# VG_CONN.net
KiCad netlist of a schematic drawn in Altium Designer
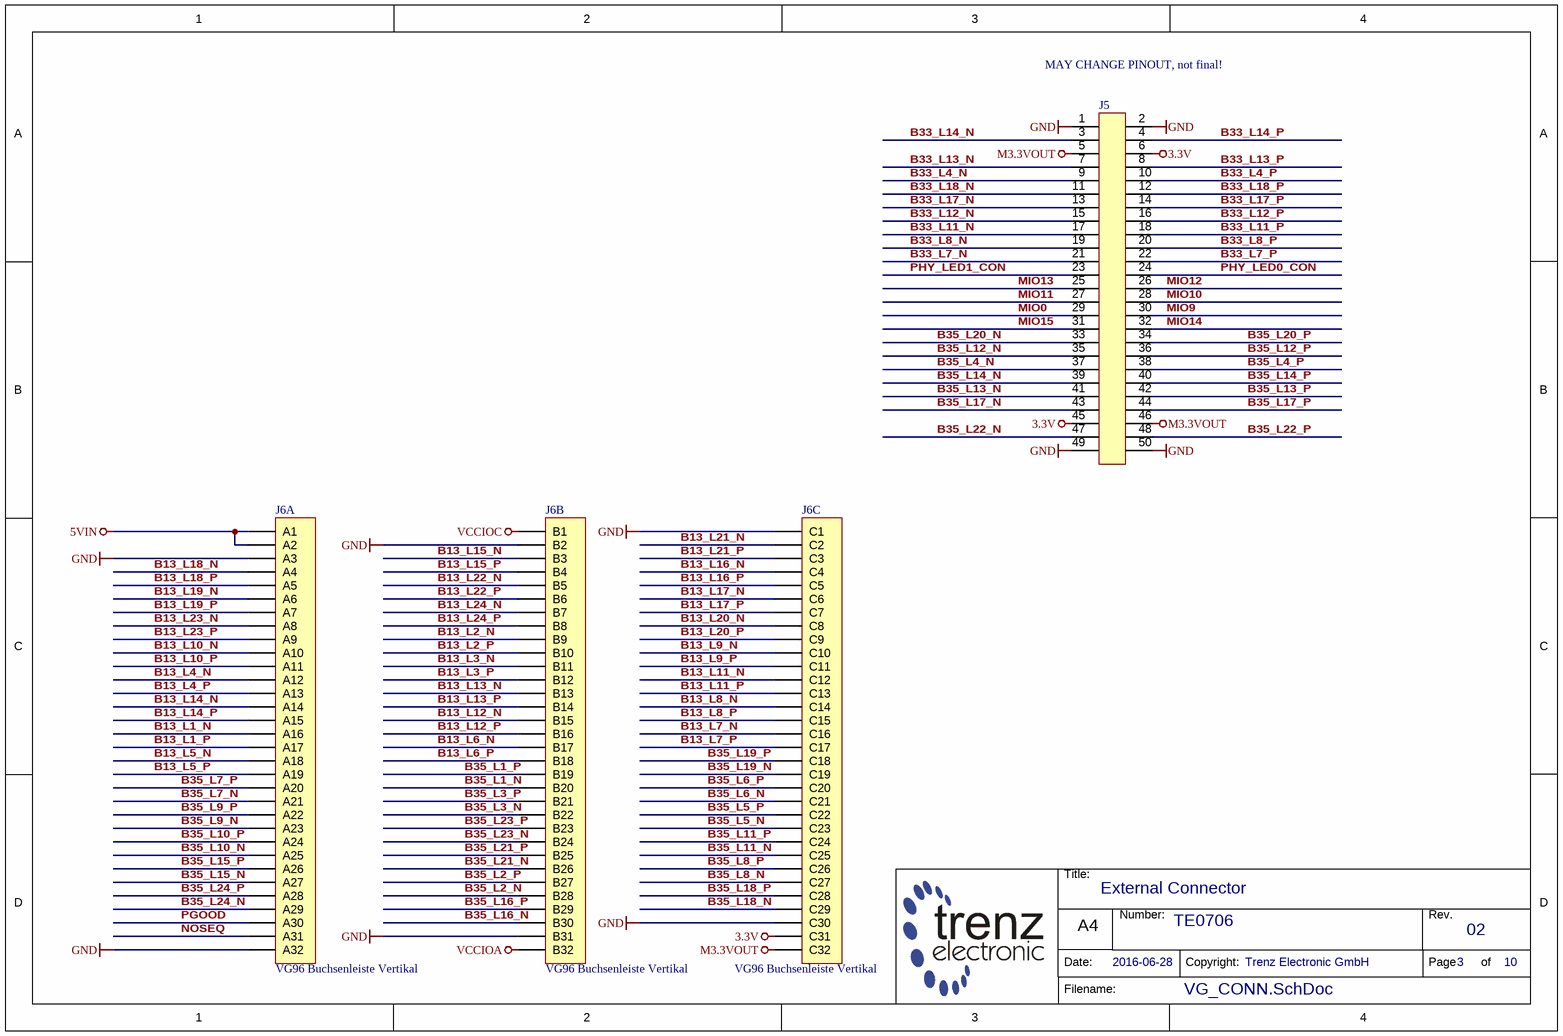
[diagram p0: VG_CONN.SchDoc]

(export (version "E")
  (design (tool "Eeschema 10.0.6"))
  (components
    (comp (ref "J5")
      (value "WANNE2,54-50 GERADE")
      (footprint "WANNE2,54-50 GERADE")
      (description "Stiftleiste Wanne 50polig")
      (libsource (lib "TE") (part "CON-50"))
    )
    (comp (ref "J6")
      (value "VG96 Buchsenleiste Vertikal")
      (footprint "VG96-F-V")
      (description "VG96 Buchsenleiste Vertikal (DIN 41612)")
      (libsource (lib "TE") (part "VG96"))
    )
  )
  (nets
    (net (code "1") (name "/B13_L1_N") (class "Default")
      (node (ref "J6") (pin "A16") (pinfunction "A16_A16") (pintype "passive"))
    )
    (net (code "2") (name "/B13_L1_P") (class "Default")
      (node (ref "J6") (pin "A17") (pinfunction "A17_A17") (pintype "passive"))
    )
    (net (code "3") (name "/B13_L2_N") (class "Default")
      (node (ref "J6") (pin "B9") (pinfunction "B9_B9") (pintype "passive"))
    )
    (net (code "4") (name "/B13_L2_P") (class "Default")
      (node (ref "J6") (pin "B10") (pinfunction "B10_B10") (pintype "passive"))
    )
    (net (code "5") (name "/B13_L3_N") (class "Default")
      (node (ref "J6") (pin "B11") (pinfunction "B11_B11") (pintype "passive"))
    )
    (net (code "6") (name "/B13_L3_P") (class "Default")
      (node (ref "J6") (pin "B12") (pinfunction "B12_B12") (pintype "passive"))
    )
    (net (code "7") (name "/B13_L4_N") (class "Default")
      (node (ref "J6") (pin "A12") (pinfunction "A12_A12") (pintype "passive"))
    )
    (net (code "8") (name "/B13_L4_P") (class "Default")
      (node (ref "J6") (pin "A13") (pinfunction "A13_A13") (pintype "passive"))
    )
    (net (code "9") (name "/B13_L5_N") (class "Default")
      (node (ref "J6") (pin "A18") (pinfunction "A18_A18") (pintype "passive"))
    )
    (net (code "10") (name "/B13_L5_P") (class "Default")
      (node (ref "J6") (pin "A19") (pinfunction "A19_A19") (pintype "passive"))
    )
    (net (code "11") (name "/B13_L6_N") (class "Default")
      (node (ref "J6") (pin "B17") (pinfunction "B17_B17") (pintype "passive"))
    )
    (net (code "12") (name "/B13_L6_P") (class "Default")
      (node (ref "J6") (pin "B18") (pinfunction "B18_B18") (pintype "passive"))
    )
    (net (code "13") (name "/B13_L7_N") (class "Default")
      (node (ref "J6") (pin "C16") (pinfunction "C16_C16") (pintype "passive"))
    )
    (net (code "14") (name "/B13_L7_P") (class "Default")
      (node (ref "J6") (pin "C17") (pinfunction "C17_C17") (pintype "passive"))
    )
    (net (code "15") (name "/B13_L8_N") (class "Default")
      (node (ref "J6") (pin "C14") (pinfunction "C14_C14") (pintype "passive"))
    )
    (net (code "16") (name "/B13_L8_P") (class "Default")
      (node (ref "J6") (pin "C15") (pinfunction "C15_C15") (pintype "passive"))
    )
    (net (code "17") (name "/B13_L9_N") (class "Default")
      (node (ref "J6") (pin "C10") (pinfunction "C10_C10") (pintype "passive"))
    )
    (net (code "18") (name "/B13_L9_P") (class "Default")
      (node (ref "J6") (pin "C11") (pinfunction "C11_C11") (pintype "passive"))
    )
    (net (code "19") (name "/B13_L10_N") (class "Default")
      (node (ref "J6") (pin "A10") (pinfunction "A10_A10") (pintype "passive"))
    )
    (net (code "20") (name "/B13_L10_P") (class "Default")
      (node (ref "J6") (pin "A11") (pinfunction "A11_A11") (pintype "passive"))
    )
    (net (code "21") (name "/B13_L11_N") (class "Default")
      (node (ref "J6") (pin "C12") (pinfunction "C12_C12") (pintype "passive"))
    )
    (net (code "22") (name "/B13_L11_P") (class "Default")
      (node (ref "J6") (pin "C13") (pinfunction "C13_C13") (pintype "passive"))
    )
    (net (code "23") (name "/B13_L12_N") (class "Default")
      (node (ref "J6") (pin "B15") (pinfunction "B15_B15") (pintype "passive"))
    )
    (net (code "24") (name "/B13_L12_P") (class "Default")
      (node (ref "J6") (pin "B16") (pinfunction "B16_B16") (pintype "passive"))
    )
    (net (code "25") (name "/B13_L13_N") (class "Default")
      (node (ref "J6") (pin "B13") (pinfunction "B13_B13") (pintype "passive"))
    )
    (net (code "26") (name "/B13_L13_P") (class "Default")
      (node (ref "J6") (pin "B14") (pinfunction "B14_B14") (pintype "passive"))
    )
    (net (code "27") (name "/B13_L14_N") (class "Default")
      (node (ref "J6") (pin "A14") (pinfunction "A14_A14") (pintype "passive"))
    )
    (net (code "28") (name "/B13_L14_P") (class "Default")
      (node (ref "J6") (pin "A15") (pinfunction "A15_A15") (pintype "passive"))
    )
    (net (code "29") (name "/B13_L15_N") (class "Default")
      (node (ref "J6") (pin "B3") (pinfunction "B3_B3") (pintype "passive"))
    )
    (net (code "30") (name "/B13_L15_P") (class "Default")
      (node (ref "J6") (pin "B4") (pinfunction "B4_B4") (pintype "passive"))
    )
    (net (code "31") (name "/B13_L16_N") (class "Default")
      (node (ref "J6") (pin "C4") (pinfunction "C4_C4") (pintype "passive"))
    )
    (net (code "32") (name "/B13_L16_P") (class "Default")
      (node (ref "J6") (pin "C5") (pinfunction "C5_C5") (pintype "passive"))
    )
    (net (code "33") (name "/B13_L17_N") (class "Default")
      (node (ref "J6") (pin "C6") (pinfunction "C6_C6") (pintype "passive"))
    )
    (net (code "34") (name "/B13_L17_P") (class "Default")
      (node (ref "J6") (pin "C7") (pinfunction "C7_C7") (pintype "passive"))
    )
    (net (code "35") (name "/B13_L18_N") (class "Default")
      (node (ref "J6") (pin "A4") (pinfunction "A4_A4") (pintype "passive"))
    )
    (net (code "36") (name "/B13_L18_P") (class "Default")
      (node (ref "J6") (pin "A5") (pinfunction "A5_A5") (pintype "passive"))
    )
    (net (code "37") (name "/B13_L19_N") (class "Default")
      (node (ref "J6") (pin "A6") (pinfunction "A6_A6") (pintype "passive"))
    )
    (net (code "38") (name "/B13_L19_P") (class "Default")
      (node (ref "J6") (pin "A7") (pinfunction "A7_A7") (pintype "passive"))
    )
    (net (code "39") (name "/B13_L20_N") (class "Default")
      (node (ref "J6") (pin "C8") (pinfunction "C8_C8") (pintype "passive"))
    )
    (net (code "40") (name "/B13_L20_P") (class "Default")
      (node (ref "J6") (pin "C9") (pinfunction "C9_C9") (pintype "passive"))
    )
    (net (code "41") (name "/B13_L21_N") (class "Default")
      (node (ref "J6") (pin "C2") (pinfunction "C2_C2") (pintype "passive"))
    )
    (net (code "42") (name "/B13_L21_P") (class "Default")
      (node (ref "J6") (pin "C3") (pinfunction "C3_C3") (pintype "passive"))
    )
    (net (code "43") (name "/B13_L22_N") (class "Default")
      (node (ref "J6") (pin "B5") (pinfunction "B5_B5") (pintype "passive"))
    )
    (net (code "44") (name "/B13_L22_P") (class "Default")
      (node (ref "J6") (pin "B6") (pinfunction "B6_B6") (pintype "passive"))
    )
    (net (code "45") (name "/B13_L23_N") (class "Default")
      (node (ref "J6") (pin "A8") (pinfunction "A8_A8") (pintype "passive"))
    )
    (net (code "46") (name "/B13_L23_P") (class "Default")
      (node (ref "J6") (pin "A9") (pinfunction "A9_A9") (pintype "passive"))
    )
    (net (code "47") (name "/B13_L24_N") (class "Default")
      (node (ref "J6") (pin "B7") (pinfunction "B7_B7") (pintype "passive"))
    )
    (net (code "48") (name "/B13_L24_P") (class "Default")
      (node (ref "J6") (pin "B8") (pinfunction "B8_B8") (pintype "passive"))
    )
    (net (code "49") (name "/B33_L4_N") (class "Default")
      (node (ref "J5") (pin "9") (pinfunction "9_9") (pintype "passive"))
    )
    (net (code "50") (name "/B33_L4_P") (class "Default")
      (node (ref "J5") (pin "10") (pinfunction "10_10") (pintype "passive"))
    )
    (net (code "51") (name "/B33_L7_N") (class "Default")
      (node (ref "J5") (pin "21") (pinfunction "21_21") (pintype "passive"))
    )
    (net (code "52") (name "/B33_L7_P") (class "Default")
      (node (ref "J5") (pin "22") (pinfunction "22_22") (pintype "passive"))
    )
    (net (code "53") (name "/B33_L8_N") (class "Default")
      (node (ref "J5") (pin "19") (pinfunction "19_19") (pintype "passive"))
    )
    (net (code "54") (name "/B33_L8_P") (class "Default")
      (node (ref "J5") (pin "20") (pinfunction "20_20") (pintype "passive"))
    )
    (net (code "55") (name "/B33_L11_N") (class "Default")
      (node (ref "J5") (pin "17") (pinfunction "17_17") (pintype "passive"))
    )
    (net (code "56") (name "/B33_L11_P") (class "Default")
      (node (ref "J5") (pin "18") (pinfunction "18_18") (pintype "passive"))
    )
    (net (code "57") (name "/B33_L12_N") (class "Default")
      (node (ref "J5") (pin "15") (pinfunction "15_15") (pintype "passive"))
    )
    (net (code "58") (name "/B33_L12_P") (class "Default")
      (node (ref "J5") (pin "16") (pinfunction "16_16") (pintype "passive"))
    )
    (net (code "59") (name "/B33_L13_N") (class "Default")
      (node (ref "J5") (pin "7") (pinfunction "7_7") (pintype "passive"))
    )
    (net (code "60") (name "/B33_L13_P") (class "Default")
      (node (ref "J5") (pin "8") (pinfunction "8_8") (pintype "passive"))
    )
    (net (code "61") (name "/B33_L14_N") (class "Default")
      (node (ref "J5") (pin "3") (pinfunction "3_3") (pintype "passive"))
    )
    (net (code "62") (name "/B33_L14_P") (class "Default")
      (node (ref "J5") (pin "4") (pinfunction "4_4") (pintype "passive"))
    )
    (net (code "63") (name "/B33_L17_N") (class "Default")
      (node (ref "J5") (pin "13") (pinfunction "13_13") (pintype "passive"))
    )
    (net (code "64") (name "/B33_L17_P") (class "Default")
      (node (ref "J5") (pin "14") (pinfunction "14_14") (pintype "passive"))
    )
    (net (code "65") (name "/B33_L18_N") (class "Default")
      (node (ref "J5") (pin "11") (pinfunction "11_11") (pintype "passive"))
    )
    (net (code "66") (name "/B33_L18_P") (class "Default")
      (node (ref "J5") (pin "12") (pinfunction "12_12") (pintype "passive"))
    )
    (net (code "67") (name "/B35_L1_N") (class "Default")
      (node (ref "J6") (pin "B20") (pinfunction "B20_B20") (pintype "passive"))
    )
    (net (code "68") (name "/B35_L1_P") (class "Default")
      (node (ref "J6") (pin "B19") (pinfunction "B19_B19") (pintype "passive"))
    )
    (net (code "69") (name "/B35_L2_N") (class "Default")
      (node (ref "J6") (pin "B28") (pinfunction "B28_B28") (pintype "passive"))
    )
    (net (code "70") (name "/B35_L2_P") (class "Default")
      (node (ref "J6") (pin "B27") (pinfunction "B27_B27") (pintype "passive"))
    )
    (net (code "71") (name "/B35_L3_N") (class "Default")
      (node (ref "J6") (pin "B22") (pinfunction "B22_B22") (pintype "passive"))
    )
    (net (code "72") (name "/B35_L3_P") (class "Default")
      (node (ref "J6") (pin "B21") (pinfunction "B21_B21") (pintype "passive"))
    )
    (net (code "73") (name "/B35_L4_N") (class "Default")
      (node (ref "J5") (pin "37") (pinfunction "37_37") (pintype "passive"))
    )
    (net (code "74") (name "/B35_L4_P") (class "Default")
      (node (ref "J5") (pin "38") (pinfunction "38_38") (pintype "passive"))
    )
    (net (code "75") (name "/B35_L5_N") (class "Default")
      (node (ref "J6") (pin "C23") (pinfunction "C23_C23") (pintype "passive"))
    )
    (net (code "76") (name "/B35_L5_P") (class "Default")
      (node (ref "J6") (pin "C22") (pinfunction "C22_C22") (pintype "passive"))
    )
    (net (code "77") (name "/B35_L6_N") (class "Default")
      (node (ref "J6") (pin "C21") (pinfunction "C21_C21") (pintype "passive"))
    )
    (net (code "78") (name "/B35_L6_P") (class "Default")
      (node (ref "J6") (pin "C20") (pinfunction "C20_C20") (pintype "passive"))
    )
    (net (code "79") (name "/B35_L7_N") (class "Default")
      (node (ref "J6") (pin "A21") (pinfunction "A21_A21") (pintype "passive"))
    )
    (net (code "80") (name "/B35_L7_P") (class "Default")
      (node (ref "J6") (pin "A20") (pinfunction "A20_A20") (pintype "passive"))
    )
    (net (code "81") (name "/B35_L8_N") (class "Default")
      (node (ref "J6") (pin "C27") (pinfunction "C27_C27") (pintype "passive"))
    )
    (net (code "82") (name "/B35_L8_P") (class "Default")
      (node (ref "J6") (pin "C26") (pinfunction "C26_C26") (pintype "passive"))
    )
    (net (code "83") (name "/B35_L9_N") (class "Default")
      (node (ref "J6") (pin "A23") (pinfunction "A23_A23") (pintype "passive"))
    )
    (net (code "84") (name "/B35_L9_P") (class "Default")
      (node (ref "J6") (pin "A22") (pinfunction "A22_A22") (pintype "passive"))
    )
    (net (code "85") (name "/B35_L10_N") (class "Default")
      (node (ref "J6") (pin "A25") (pinfunction "A25_A25") (pintype "passive"))
    )
    (net (code "86") (name "/B35_L10_P") (class "Default")
      (node (ref "J6") (pin "A24") (pinfunction "A24_A24") (pintype "passive"))
    )
    (net (code "87") (name "/B35_L11_N") (class "Default")
      (node (ref "J6") (pin "C25") (pinfunction "C25_C25") (pintype "passive"))
    )
    (net (code "88") (name "/B35_L11_P") (class "Default")
      (node (ref "J6") (pin "C24") (pinfunction "C24_C24") (pintype "passive"))
    )
    (net (code "89") (name "/B35_L12_N") (class "Default")
      (node (ref "J5") (pin "35") (pinfunction "35_35") (pintype "passive"))
    )
    (net (code "90") (name "/B35_L12_P") (class "Default")
      (node (ref "J5") (pin "36") (pinfunction "36_36") (pintype "passive"))
    )
    (net (code "91") (name "/B35_L13_N") (class "Default")
      (node (ref "J5") (pin "41") (pinfunction "41_41") (pintype "passive"))
    )
    (net (code "92") (name "/B35_L13_P") (class "Default")
      (node (ref "J5") (pin "42") (pinfunction "42_42") (pintype "passive"))
    )
    (net (code "93") (name "/B35_L14_N") (class "Default")
      (node (ref "J5") (pin "39") (pinfunction "39_39") (pintype "passive"))
    )
    (net (code "94") (name "/B35_L14_P") (class "Default")
      (node (ref "J5") (pin "40") (pinfunction "40_40") (pintype "passive"))
    )
    (net (code "95") (name "/B35_L15_N") (class "Default")
      (node (ref "J6") (pin "A27") (pinfunction "A27_A27") (pintype "passive"))
    )
    (net (code "96") (name "/B35_L15_P") (class "Default")
      (node (ref "J6") (pin "A26") (pinfunction "A26_A26") (pintype "passive"))
    )
    (net (code "97") (name "/B35_L16_N") (class "Default")
      (node (ref "J6") (pin "B30") (pinfunction "B30_B30") (pintype "passive"))
    )
    (net (code "98") (name "/B35_L16_P") (class "Default")
      (node (ref "J6") (pin "B29") (pinfunction "B29_B29") (pintype "passive"))
    )
    (net (code "99") (name "/B35_L17_N") (class "Default")
      (node (ref "J5") (pin "43") (pinfunction "43_43") (pintype "passive"))
    )
    (net (code "100") (name "/B35_L17_P") (class "Default")
      (node (ref "J5") (pin "44") (pinfunction "44_44") (pintype "passive"))
    )
    (net (code "101") (name "/B35_L18_N") (class "Default")
      (node (ref "J6") (pin "C29") (pinfunction "C29_C29") (pintype "passive"))
    )
    (net (code "102") (name "/B35_L18_P") (class "Default")
      (node (ref "J6") (pin "C28") (pinfunction "C28_C28") (pintype "passive"))
    )
    (net (code "103") (name "/B35_L19_N") (class "Default")
      (node (ref "J6") (pin "C19") (pinfunction "C19_C19") (pintype "passive"))
    )
    (net (code "104") (name "/B35_L19_P") (class "Default")
      (node (ref "J6") (pin "C18") (pinfunction "C18_C18") (pintype "passive"))
    )
    (net (code "105") (name "/B35_L20_N") (class "Default")
      (node (ref "J5") (pin "33") (pinfunction "33_33") (pintype "passive"))
    )
    (net (code "106") (name "/B35_L20_P") (class "Default")
      (node (ref "J5") (pin "34") (pinfunction "34_34") (pintype "passive"))
    )
    (net (code "107") (name "/B35_L21_N") (class "Default")
      (node (ref "J6") (pin "B26") (pinfunction "B26_B26") (pintype "passive"))
    )
    (net (code "108") (name "/B35_L21_P") (class "Default")
      (node (ref "J6") (pin "B25") (pinfunction "B25_B25") (pintype "passive"))
    )
    (net (code "109") (name "/B35_L22_N") (class "Default")
      (node (ref "J5") (pin "47") (pinfunction "47_47") (pintype "passive"))
    )
    (net (code "110") (name "/B35_L22_P") (class "Default")
      (node (ref "J5") (pin "48") (pinfunction "48_48") (pintype "passive"))
    )
    (net (code "111") (name "/B35_L23_N") (class "Default")
      (node (ref "J6") (pin "B24") (pinfunction "B24_B24") (pintype "passive"))
    )
    (net (code "112") (name "/B35_L23_P") (class "Default")
      (node (ref "J6") (pin "B23") (pinfunction "B23_B23") (pintype "passive"))
    )
    (net (code "113") (name "/B35_L24_N") (class "Default")
      (node (ref "J6") (pin "A29") (pinfunction "A29_A29") (pintype "passive"))
    )
    (net (code "114") (name "/B35_L24_P") (class "Default")
      (node (ref "J6") (pin "A28") (pinfunction "A28_A28") (pintype "passive"))
    )
    (net (code "115") (name "/MIO0") (class "Default")
      (node (ref "J5") (pin "29") (pinfunction "29_29") (pintype "passive"))
    )
    (net (code "116") (name "/MIO9") (class "Default")
      (node (ref "J5") (pin "30") (pinfunction "30_30") (pintype "passive"))
    )
    (net (code "117") (name "/MIO10") (class "Default")
      (node (ref "J5") (pin "28") (pinfunction "28_28") (pintype "passive"))
    )
    (net (code "118") (name "/MIO11") (class "Default")
      (node (ref "J5") (pin "27") (pinfunction "27_27") (pintype "passive"))
    )
    (net (code "119") (name "/MIO12") (class "Default")
      (node (ref "J5") (pin "26") (pinfunction "26_26") (pintype "passive"))
    )
    (net (code "120") (name "/MIO13") (class "Default")
      (node (ref "J5") (pin "25") (pinfunction "25_25") (pintype "passive"))
    )
    (net (code "121") (name "/MIO14") (class "Default")
      (node (ref "J5") (pin "32") (pinfunction "32_32") (pintype "passive"))
    )
    (net (code "122") (name "/MIO15") (class "Default")
      (node (ref "J5") (pin "31") (pinfunction "31_31") (pintype "passive"))
    )
    (net (code "123") (name "/NOSEQ") (class "Default")
      (node (ref "J6") (pin "A31") (pinfunction "A31_A31") (pintype "passive"))
    )
    (net (code "124") (name "/PGOOD") (class "Default")
      (node (ref "J6") (pin "A30") (pinfunction "A30_A30") (pintype "passive"))
    )
    (net (code "125") (name "/PHY_LED0_CON") (class "Default")
      (node (ref "J5") (pin "24") (pinfunction "24_24") (pintype "passive"))
    )
    (net (code "126") (name "/PHY_LED1_CON") (class "Default")
      (node (ref "J5") (pin "23") (pinfunction "23_23") (pintype "passive"))
    )
    (net (code "127") (name "3.3V") (class "Default")
      (node (ref "J5") (pin "45") (pinfunction "45_45") (pintype "passive"))
      (node (ref "J5") (pin "6") (pinfunction "6_6") (pintype "passive"))
      (node (ref "J6") (pin "C31") (pinfunction "C31_C31") (pintype "passive"))
    )
    (net (code "128") (name "5VIN") (class "Default")
      (node (ref "J6") (pin "A1") (pinfunction "A1_A1") (pintype "passive"))
      (node (ref "J6") (pin "A2") (pinfunction "A2_A2") (pintype "passive"))
    )
    (net (code "129") (name "GND") (class "Default")
      (node (ref "J5") (pin "1") (pinfunction "1_1") (pintype "passive"))
      (node (ref "J5") (pin "2") (pinfunction "2_2") (pintype "passive"))
      (node (ref "J5") (pin "49") (pinfunction "49_49") (pintype "passive"))
      (node (ref "J5") (pin "50") (pinfunction "50_50") (pintype "passive"))
      (node (ref "J6") (pin "A3") (pinfunction "A3_A3") (pintype "passive"))
      (node (ref "J6") (pin "A32") (pinfunction "A32_A32") (pintype "passive"))
      (node (ref "J6") (pin "B2") (pinfunction "B2_B2") (pintype "passive"))
      (node (ref "J6") (pin "B31") (pinfunction "B31_B31") (pintype "passive"))
      (node (ref "J6") (pin "C1") (pinfunction "C1_C1") (pintype "passive"))
      (node (ref "J6") (pin "C30") (pinfunction "C30_C30") (pintype "passive"))
    )
    (net (code "130") (name "M3.3VOUT") (class "Default")
      (node (ref "J5") (pin "46") (pinfunction "46_46") (pintype "passive"))
      (node (ref "J5") (pin "5") (pinfunction "5_5") (pintype "passive"))
      (node (ref "J6") (pin "C32") (pinfunction "C32_C32") (pintype "passive"))
    )
    (net (code "131") (name "VCCIOA") (class "Default")
      (node (ref "J6") (pin "B32") (pinfunction "B32_B32") (pintype "passive"))
    )
    (net (code "132") (name "VCCIOC") (class "Default")
      (node (ref "J6") (pin "B1") (pinfunction "B1_B1") (pintype "passive"))
    )
  )
)
